# Firefly.net
KiCad netlist of a schematic drawn in EAGLE
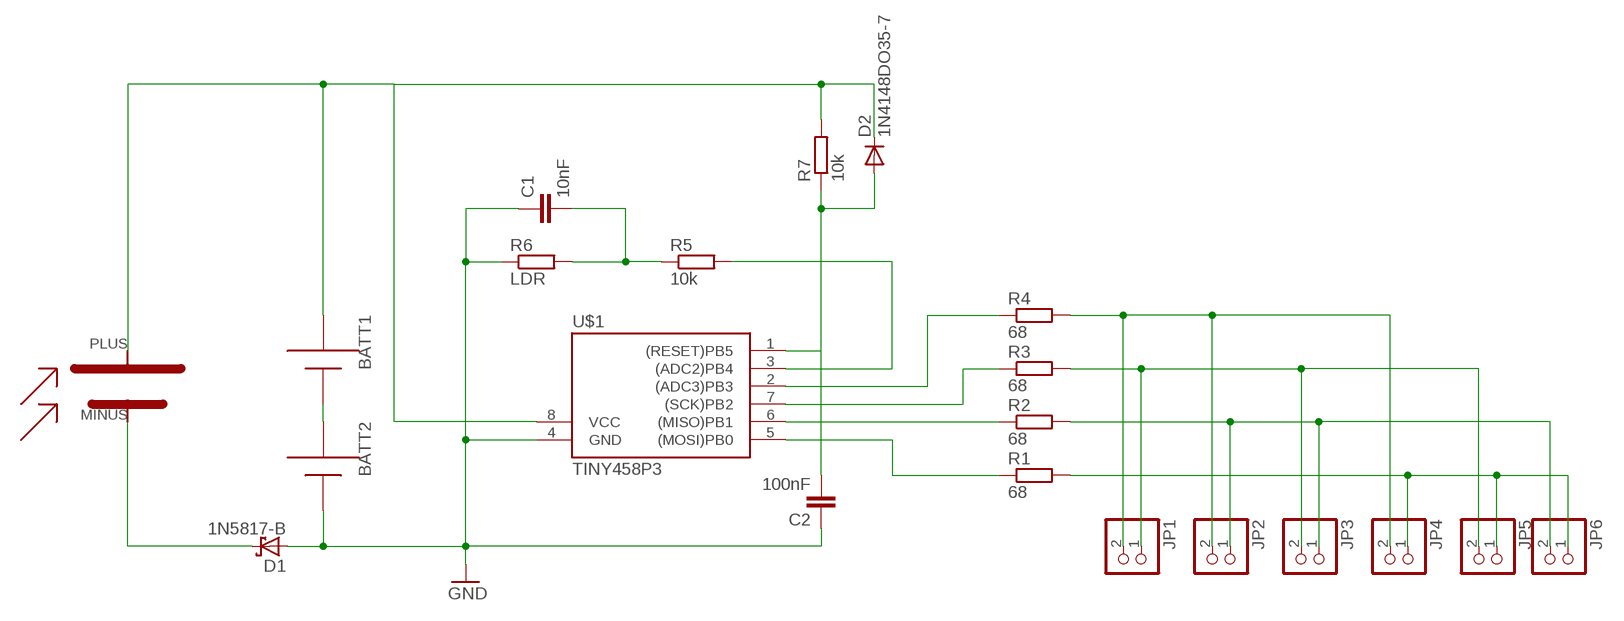
[diagram p0: schematic, sheet 1]

(export (version "E")
  (design (tool "Eeschema 10.0.6"))
  (components
    (comp (ref "BATT1")
      (value "AAA")
      (footprint "eagle-import:12BH412")
      (libsource (lib "eagle-import") (part "AAA"))
    )
    (comp (ref "BATT2")
      (value "AAA")
      (footprint "eagle-import:12BH412")
      (libsource (lib "eagle-import") (part "AAA"))
    )
    (comp (ref "C1")
      (value "10nF")
      (footprint "eagle-import:C025-025X050")
      (libsource (lib "eagle-import") (part "C-EU025-025X050"))
    )
    (comp (ref "C2")
      (value "100nF")
      (footprint "eagle-import:C075-032X103")
      (libsource (lib "eagle-import") (part "C-EU075-032X103"))
    )
    (comp (ref "D1")
      (value "1N5817-B")
      (footprint "eagle-import:DO41-7.6")
      (libsource (lib "eagle-import") (part "1N5817-B"))
    )
    (comp (ref "D2")
      (value "1N4148DO35-7")
      (footprint "eagle-import:DO35-7")
      (libsource (lib "eagle-import") (part "1N4148DO35-7"))
    )
    (comp (ref "JP1")
      (value "PINHD-1X2")
      (footprint "eagle-import:1X02")
      (libsource (lib "eagle-import") (part "PINHD-1X2"))
    )
    (comp (ref "JP2")
      (value "PINHD-1X2")
      (footprint "eagle-import:1X02")
      (libsource (lib "eagle-import") (part "PINHD-1X2"))
    )
    (comp (ref "JP3")
      (value "PINHD-1X2")
      (footprint "eagle-import:1X02")
      (libsource (lib "eagle-import") (part "PINHD-1X2"))
    )
    (comp (ref "JP4")
      (value "PINHD-1X2")
      (footprint "eagle-import:1X02")
      (libsource (lib "eagle-import") (part "PINHD-1X2"))
    )
    (comp (ref "JP5")
      (value "PINHD-1X2")
      (footprint "eagle-import:1X02")
      (libsource (lib "eagle-import") (part "PINHD-1X2"))
    )
    (comp (ref "JP6")
      (value "PINHD-1X2")
      (footprint "eagle-import:1X02")
      (libsource (lib "eagle-import") (part "PINHD-1X2"))
    )
    (comp (ref "R1")
      (value "68")
      (footprint "eagle-import:0204_7")
      (libsource (lib "eagle-import") (part "R-EU_0204/7"))
    )
    (comp (ref "R2")
      (value "68")
      (footprint "eagle-import:0204_7")
      (libsource (lib "eagle-import") (part "R-EU_0204/7"))
    )
    (comp (ref "R3")
      (value "68")
      (footprint "eagle-import:0204_7")
      (libsource (lib "eagle-import") (part "R-EU_0204/7"))
    )
    (comp (ref "R4")
      (value "68")
      (footprint "eagle-import:0204_7")
      (libsource (lib "eagle-import") (part "R-EU_0204/7"))
    )
    (comp (ref "R5")
      (value "10k")
      (footprint "eagle-import:0207_10")
      (libsource (lib "eagle-import") (part "R-EU_0207/10"))
    )
    (comp (ref "R6")
      (value "LDR")
      (footprint "eagle-import:0204_7")
      (libsource (lib "eagle-import") (part "R-EU_0204/7"))
    )
    (comp (ref "R7")
      (value "10k")
      (footprint "eagle-import:0204_7")
      (libsource (lib "eagle-import") (part "R-EU_0204/7"))
    )
    (comp (ref "U$1")
      (value "TINY458P3")
      (footprint "eagle-import:DIL08")
      (libsource (lib "eagle-import") (part "TINY458P3"))
    )
    (comp (ref "U$2")
      (value "SOLARCELL4V35MACONRAD")
      (footprint "eagle-import:SOLARCELL35X39")
      (libsource (lib "eagle-import") (part "SOLARCELL4V35MACONRAD"))
    )
  )
  (nets
    (net (code "1") (name "GND") (class "Default")
      (node (ref "BATT2") (pin "-") (pinfunction "-_-") (pintype "bidirectional"))
      (node (ref "C1") (pin "1") (pinfunction "1_1") (pintype "passive"))
      (node (ref "C2") (pin "1") (pinfunction "1_1") (pintype "passive"))
      (node (ref "D1") (pin "A") (pinfunction "A_A") (pintype "passive"))
      (node (ref "R6") (pin "1") (pinfunction "1_1") (pintype "passive"))
      (node (ref "U$1") (pin "4") (pinfunction "GND_4") (pintype "power_in"))
    )
    (net (code "2") (name "Net-(BATT1-Pad-)") (class "Default")
      (node (ref "BATT1") (pin "-") (pinfunction "-_-") (pintype "bidirectional"))
      (node (ref "BATT2") (pin "+") (pinfunction "+_+") (pintype "bidirectional"))
    )
    (net (code "3") (name "Net-(C1-Pad2)") (class "Default")
      (node (ref "C1") (pin "2") (pinfunction "2_2") (pintype "passive"))
      (node (ref "R5") (pin "1") (pinfunction "1_1") (pintype "passive"))
      (node (ref "R6") (pin "2") (pinfunction "2_2") (pintype "passive"))
    )
    (net (code "4") (name "Net-(D1-PadC)") (class "Default")
      (node (ref "D1") (pin "C") (pinfunction "C_C") (pintype "passive"))
      (node (ref "U$2") (pin "MINUS") (pinfunction "MINUS_MINUS") (pintype "power_in"))
    )
    (net (code "5") (name "Net-(JP1-Pad1)") (class "Default")
      (node (ref "JP1") (pin "1") (pinfunction "1_1") (pintype "passive"))
      (node (ref "JP3") (pin "2") (pinfunction "2_2") (pintype "passive"))
      (node (ref "JP5") (pin "2") (pinfunction "2_2") (pintype "passive"))
      (node (ref "R3") (pin "2") (pinfunction "2_2") (pintype "passive"))
    )
    (net (code "6") (name "Net-(JP1-Pad2)") (class "Default")
      (node (ref "JP1") (pin "2") (pinfunction "2_2") (pintype "passive"))
      (node (ref "JP2") (pin "2") (pinfunction "2_2") (pintype "passive"))
      (node (ref "JP4") (pin "2") (pinfunction "2_2") (pintype "passive"))
      (node (ref "R4") (pin "2") (pinfunction "2_2") (pintype "passive"))
    )
    (net (code "7") (name "Net-(JP2-Pad1)") (class "Default")
      (node (ref "JP2") (pin "1") (pinfunction "1_1") (pintype "passive"))
      (node (ref "JP3") (pin "1") (pinfunction "1_1") (pintype "passive"))
      (node (ref "JP6") (pin "2") (pinfunction "2_2") (pintype "passive"))
      (node (ref "R2") (pin "2") (pinfunction "2_2") (pintype "passive"))
    )
    (net (code "8") (name "Net-(JP4-Pad1)") (class "Default")
      (node (ref "JP4") (pin "1") (pinfunction "1_1") (pintype "passive"))
      (node (ref "JP5") (pin "1") (pinfunction "1_1") (pintype "passive"))
      (node (ref "JP6") (pin "1") (pinfunction "1_1") (pintype "passive"))
      (node (ref "R1") (pin "2") (pinfunction "2_2") (pintype "passive"))
    )
    (net (code "9") (name "Net-(U$1-(ADC2)PB4)") (class "Default")
      (node (ref "R5") (pin "2") (pinfunction "2_2") (pintype "passive"))
      (node (ref "U$1") (pin "3") (pinfunction "(ADC2)PB4_3") (pintype "bidirectional"))
    )
    (net (code "10") (name "Net-(U$1-(ADC3)PB3)") (class "Default")
      (node (ref "R4") (pin "1") (pinfunction "1_1") (pintype "passive"))
      (node (ref "U$1") (pin "2") (pinfunction "(ADC3)PB3_2") (pintype "bidirectional"))
    )
    (net (code "11") (name "Net-(U$1-(MISO)PB1)") (class "Default")
      (node (ref "R2") (pin "1") (pinfunction "1_1") (pintype "passive"))
      (node (ref "U$1") (pin "6") (pinfunction "(MISO)PB1_6") (pintype "bidirectional"))
    )
    (net (code "12") (name "Net-(U$1-(MOSI)PB0)") (class "Default")
      (node (ref "R1") (pin "1") (pinfunction "1_1") (pintype "passive"))
      (node (ref "U$1") (pin "5") (pinfunction "(MOSI)PB0_5") (pintype "bidirectional"))
    )
    (net (code "13") (name "Net-(U$1-(RESET)PB5)") (class "Default")
      (node (ref "C2") (pin "2") (pinfunction "2_2") (pintype "passive"))
      (node (ref "D2") (pin "A") (pinfunction "A_A") (pintype "passive"))
      (node (ref "R7") (pin "1") (pinfunction "1_1") (pintype "passive"))
      (node (ref "U$1") (pin "1") (pinfunction "(RESET)PB5_1") (pintype "bidirectional"))
    )
    (net (code "14") (name "Net-(U$1-(SCK)PB2)") (class "Default")
      (node (ref "R3") (pin "1") (pinfunction "1_1") (pintype "passive"))
      (node (ref "U$1") (pin "7") (pinfunction "(SCK)PB2_7") (pintype "bidirectional"))
    )
    (net (code "15") (name "Net-(U$1-VCC)") (class "Default")
      (node (ref "BATT1") (pin "+") (pinfunction "+_+") (pintype "bidirectional"))
      (node (ref "D2") (pin "C") (pinfunction "C_C") (pintype "passive"))
      (node (ref "R7") (pin "2") (pinfunction "2_2") (pintype "passive"))
      (node (ref "U$1") (pin "8") (pinfunction "VCC_8") (pintype "power_in"))
      (node (ref "U$2") (pin "PLUS") (pinfunction "PLUS_PLUS") (pintype "power_in"))
    )
  )
)
